# C64_AV-Adaptor.net
KiCad netlist of a schematic drawn in EAGLE
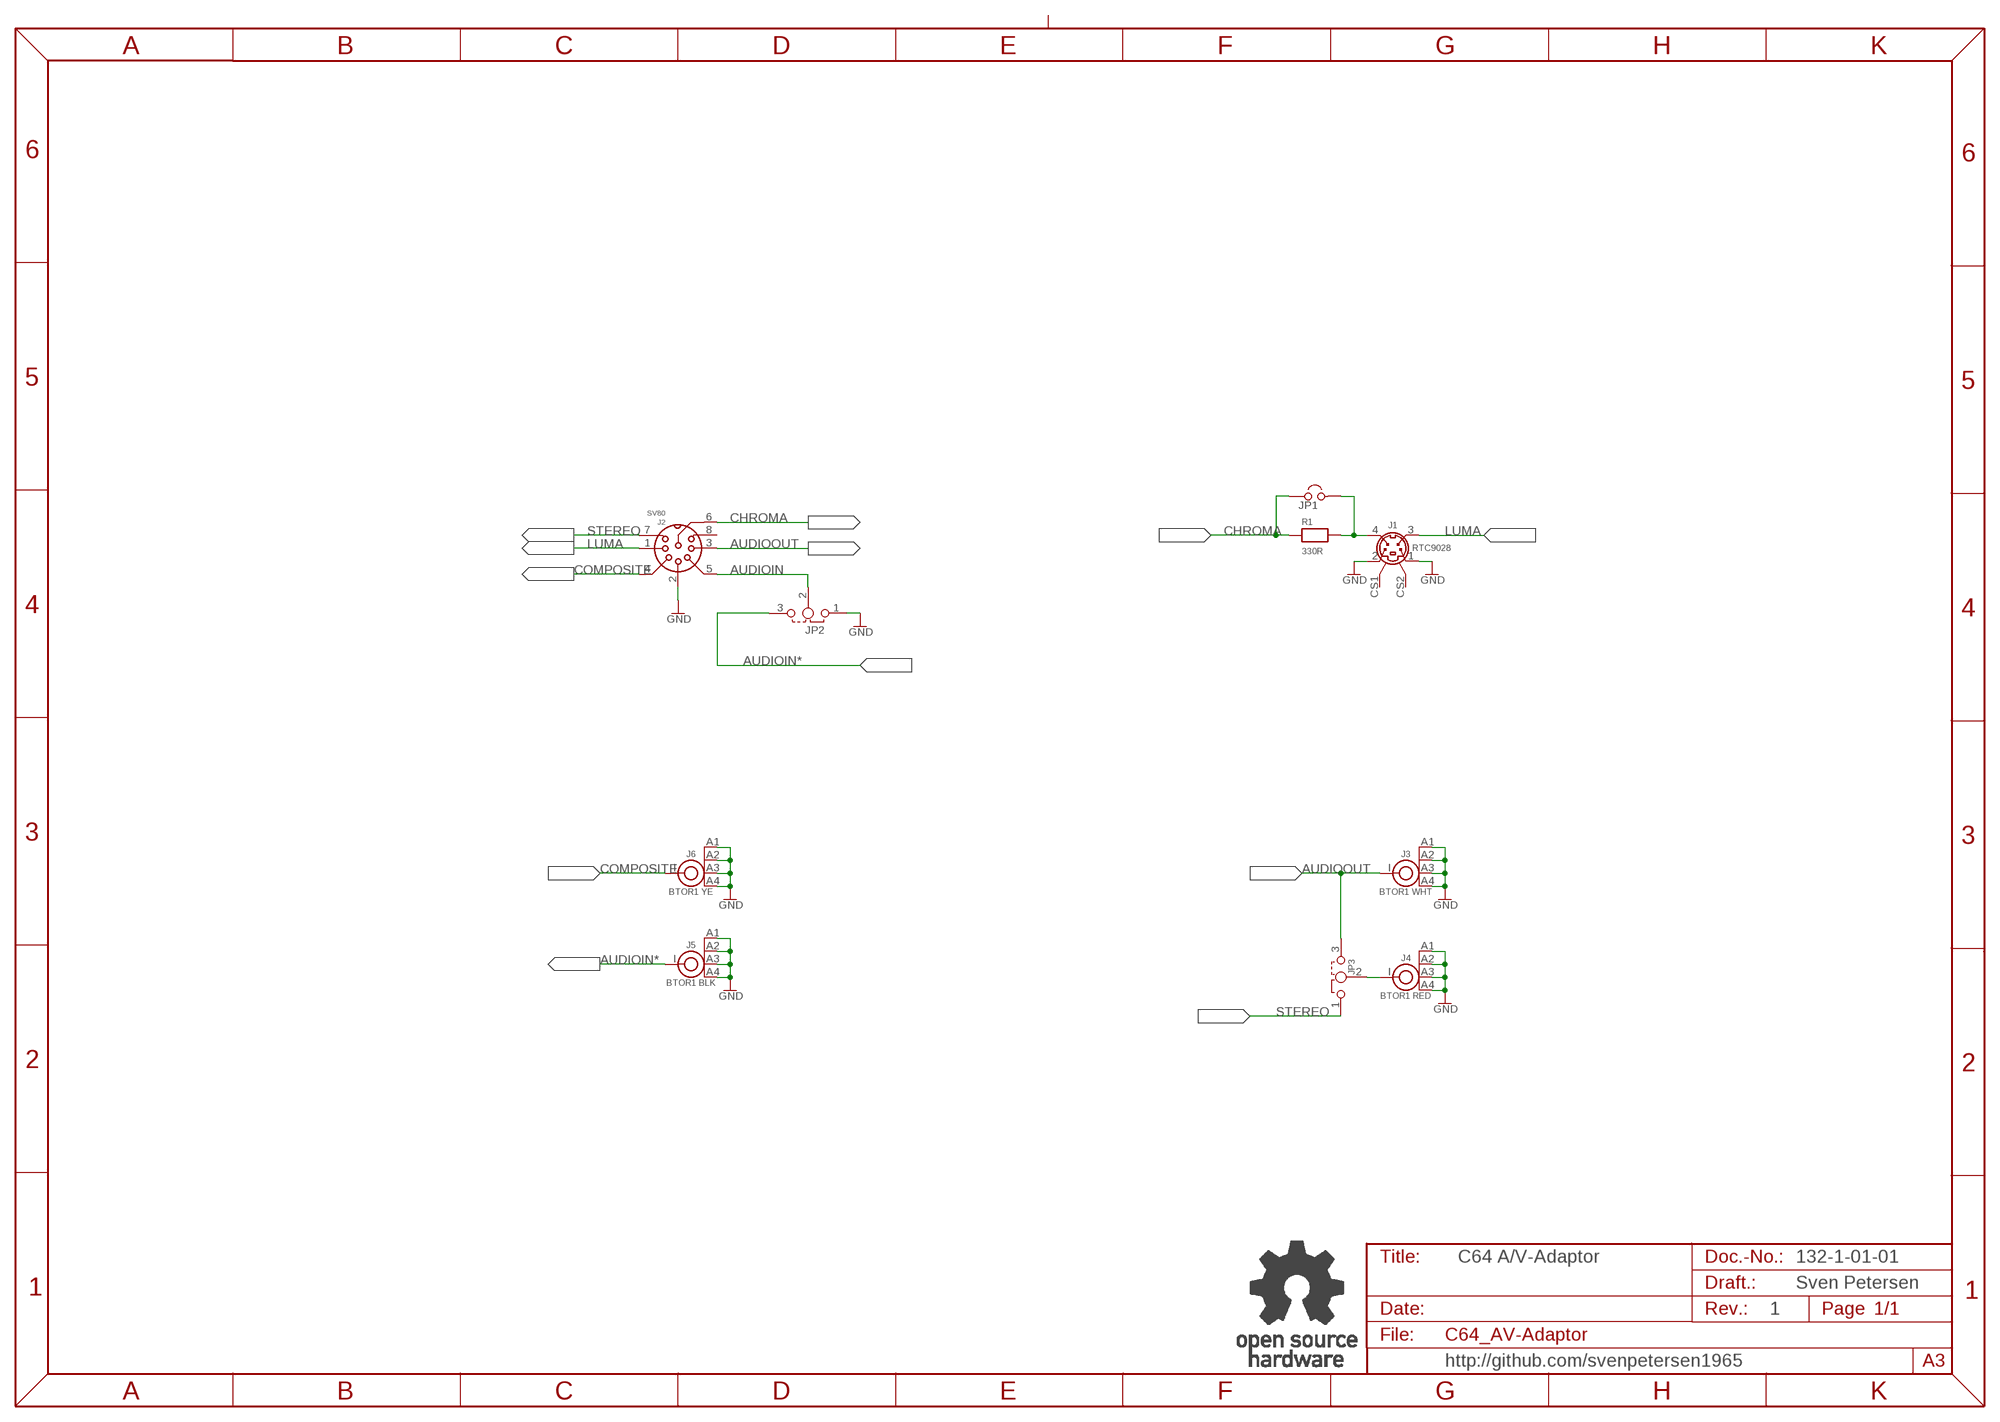
[diagram p0: schematic, sheet 1]

(export (version "E")
  (design (tool "Eeschema 10.0.6"))
  (components
    (comp (ref "J1")
      (value "RTC9028")
      (footprint "eagle-import:MINIDIN4_V")
      (libsource (lib "eagle-import") (part "RTC9028"))
    )
    (comp (ref "J2")
      (value "SV80")
      (footprint "eagle-import:SV80_INNER")
      (libsource (lib "eagle-import") (part "SV80"))
    )
    (comp (ref "J3")
      (value "BTOR1 WHT")
      (footprint "eagle-import:BTOR1")
      (libsource (lib "eagle-import") (part "BTOR1"))
    )
    (comp (ref "J4")
      (value "BTOR1 RED")
      (footprint "eagle-import:BTOR1")
      (libsource (lib "eagle-import") (part "BTOR1"))
    )
    (comp (ref "J5")
      (value "BTOR1 BLK")
      (footprint "eagle-import:BTOR1")
      (libsource (lib "eagle-import") (part "BTOR1"))
    )
    (comp (ref "J6")
      (value "BTOR1 YE")
      (footprint "eagle-import:BTOR1")
      (libsource (lib "eagle-import") (part "BTOR1"))
    )
    (comp (ref "JP1")
      (value "JUMPER")
      (footprint "eagle-import:1X02")
      (libsource (lib "eagle-import") (part "JUMPER"))
    )
    (comp (ref "JP2")
      (value "DJUMPER")
      (footprint "eagle-import:1X03")
      (libsource (lib "eagle-import") (part "DJUMPER"))
    )
    (comp (ref "JP3")
      (value "DJUMPER")
      (footprint "eagle-import:1X03")
      (libsource (lib "eagle-import") (part "DJUMPER"))
    )
    (comp (ref "R1")
      (value "330R")
      (footprint "eagle-import:R-10")
      (libsource (lib "eagle-import") (part "RES04"))
    )
    (comp (ref "U$25")
      (value "OPEN_SOURCE_HW")
      (footprint "eagle-import:OPENHW")
      (libsource (lib "eagle-import") (part "OPEN_SOURCE_HW"))
    )
  )
  (nets
    (net (code "1") (name "/AUDIOIN") (class "Default")
      (node (ref "J2") (pin "5") (pinfunction "5_5") (pintype "bidirectional"))
      (node (ref "JP2") (pin "2") (pinfunction "2_2") (pintype "bidirectional"))
    )
    (net (code "2") (name "/AUDIOIN*") (class "Default")
      (node (ref "J5") (pin "I") (pinfunction "I_I") (pintype "bidirectional"))
      (node (ref "JP2") (pin "3") (pinfunction "3_3") (pintype "bidirectional"))
    )
    (net (code "3") (name "/AUDIOOUT") (class "Default")
      (node (ref "J2") (pin "3") (pinfunction "3_3") (pintype "bidirectional"))
      (node (ref "J3") (pin "I") (pinfunction "I_I") (pintype "bidirectional"))
      (node (ref "JP3") (pin "3") (pinfunction "3_3") (pintype "bidirectional"))
    )
    (net (code "4") (name "/CHROMA") (class "Default")
      (node (ref "J2") (pin "6") (pinfunction "6_6") (pintype "bidirectional"))
      (node (ref "JP1") (pin "1") (pinfunction "1_1") (pintype "bidirectional"))
      (node (ref "R1") (pin "1") (pinfunction "1_1") (pintype "passive"))
    )
    (net (code "5") (name "/COMPOSITE") (class "Default")
      (node (ref "J2") (pin "4") (pinfunction "4_4") (pintype "bidirectional"))
      (node (ref "J6") (pin "I") (pinfunction "I_I") (pintype "bidirectional"))
    )
    (net (code "6") (name "/LUMA") (class "Default")
      (node (ref "J1") (pin "3") (pinfunction "3_3") (pintype "bidirectional"))
      (node (ref "J2") (pin "1") (pinfunction "1_1") (pintype "bidirectional"))
    )
    (net (code "7") (name "/STEREO") (class "Default")
      (node (ref "J2") (pin "7") (pinfunction "7_7") (pintype "bidirectional"))
      (node (ref "JP3") (pin "1") (pinfunction "1_1") (pintype "bidirectional"))
    )
    (net (code "8") (name "GND") (class "Default")
      (node (ref "J1") (pin "1") (pinfunction "1_1") (pintype "bidirectional"))
      (node (ref "J1") (pin "2") (pinfunction "2_2") (pintype "bidirectional"))
      (node (ref "J2") (pin "2") (pinfunction "2_2") (pintype "bidirectional"))
      (node (ref "J3") (pin "A1") (pinfunction "A1_A1") (pintype "bidirectional"))
      (node (ref "J3") (pin "A2") (pinfunction "A2_A2") (pintype "bidirectional"))
      (node (ref "J3") (pin "A3") (pinfunction "A3_A3") (pintype "bidirectional"))
      (node (ref "J3") (pin "A4") (pinfunction "A4_A4") (pintype "bidirectional"))
      (node (ref "J4") (pin "A1") (pinfunction "A1_A1") (pintype "bidirectional"))
      (node (ref "J4") (pin "A2") (pinfunction "A2_A2") (pintype "bidirectional"))
      (node (ref "J4") (pin "A3") (pinfunction "A3_A3") (pintype "bidirectional"))
      (node (ref "J4") (pin "A4") (pinfunction "A4_A4") (pintype "bidirectional"))
      (node (ref "J5") (pin "A1") (pinfunction "A1_A1") (pintype "bidirectional"))
      (node (ref "J5") (pin "A2") (pinfunction "A2_A2") (pintype "bidirectional"))
      (node (ref "J5") (pin "A3") (pinfunction "A3_A3") (pintype "bidirectional"))
      (node (ref "J5") (pin "A4") (pinfunction "A4_A4") (pintype "bidirectional"))
      (node (ref "J6") (pin "A1") (pinfunction "A1_A1") (pintype "bidirectional"))
      (node (ref "J6") (pin "A2") (pinfunction "A2_A2") (pintype "bidirectional"))
      (node (ref "J6") (pin "A3") (pinfunction "A3_A3") (pintype "bidirectional"))
      (node (ref "J6") (pin "A4") (pinfunction "A4_A4") (pintype "bidirectional"))
      (node (ref "JP2") (pin "1") (pinfunction "1_1") (pintype "bidirectional"))
    )
    (net (code "9") (name "Net-(J1-Pad4)") (class "Default")
      (node (ref "J1") (pin "4") (pinfunction "4_4") (pintype "bidirectional"))
      (node (ref "JP1") (pin "2") (pinfunction "2_2") (pintype "bidirectional"))
      (node (ref "R1") (pin "2") (pinfunction "2_2") (pintype "passive"))
    )
    (net (code "10") (name "Net-(J4-PadI)") (class "Default")
      (node (ref "J4") (pin "I") (pinfunction "I_I") (pintype "bidirectional"))
      (node (ref "JP3") (pin "2") (pinfunction "2_2") (pintype "bidirectional"))
    )
    (net (code "11") (name "unconnected-(J1-PadCS1)") (class "Default")
      (node (ref "J1") (pin "CS1") (pinfunction "CS1_CS1") (pintype "bidirectional"))
    )
    (net (code "12") (name "unconnected-(J1-PadCS2)") (class "Default")
      (node (ref "J1") (pin "CS2") (pinfunction "CS2_CS2") (pintype "bidirectional"))
    )
    (net (code "13") (name "unconnected-(J2-Pad8)") (class "Default")
      (node (ref "J2") (pin "8") (pinfunction "8_8") (pintype "bidirectional"))
    )
  )
)
